# TELM0005_TempSenseHIGH_BCR.net
KiCad netlist of a schematic drawn in Altium Designer
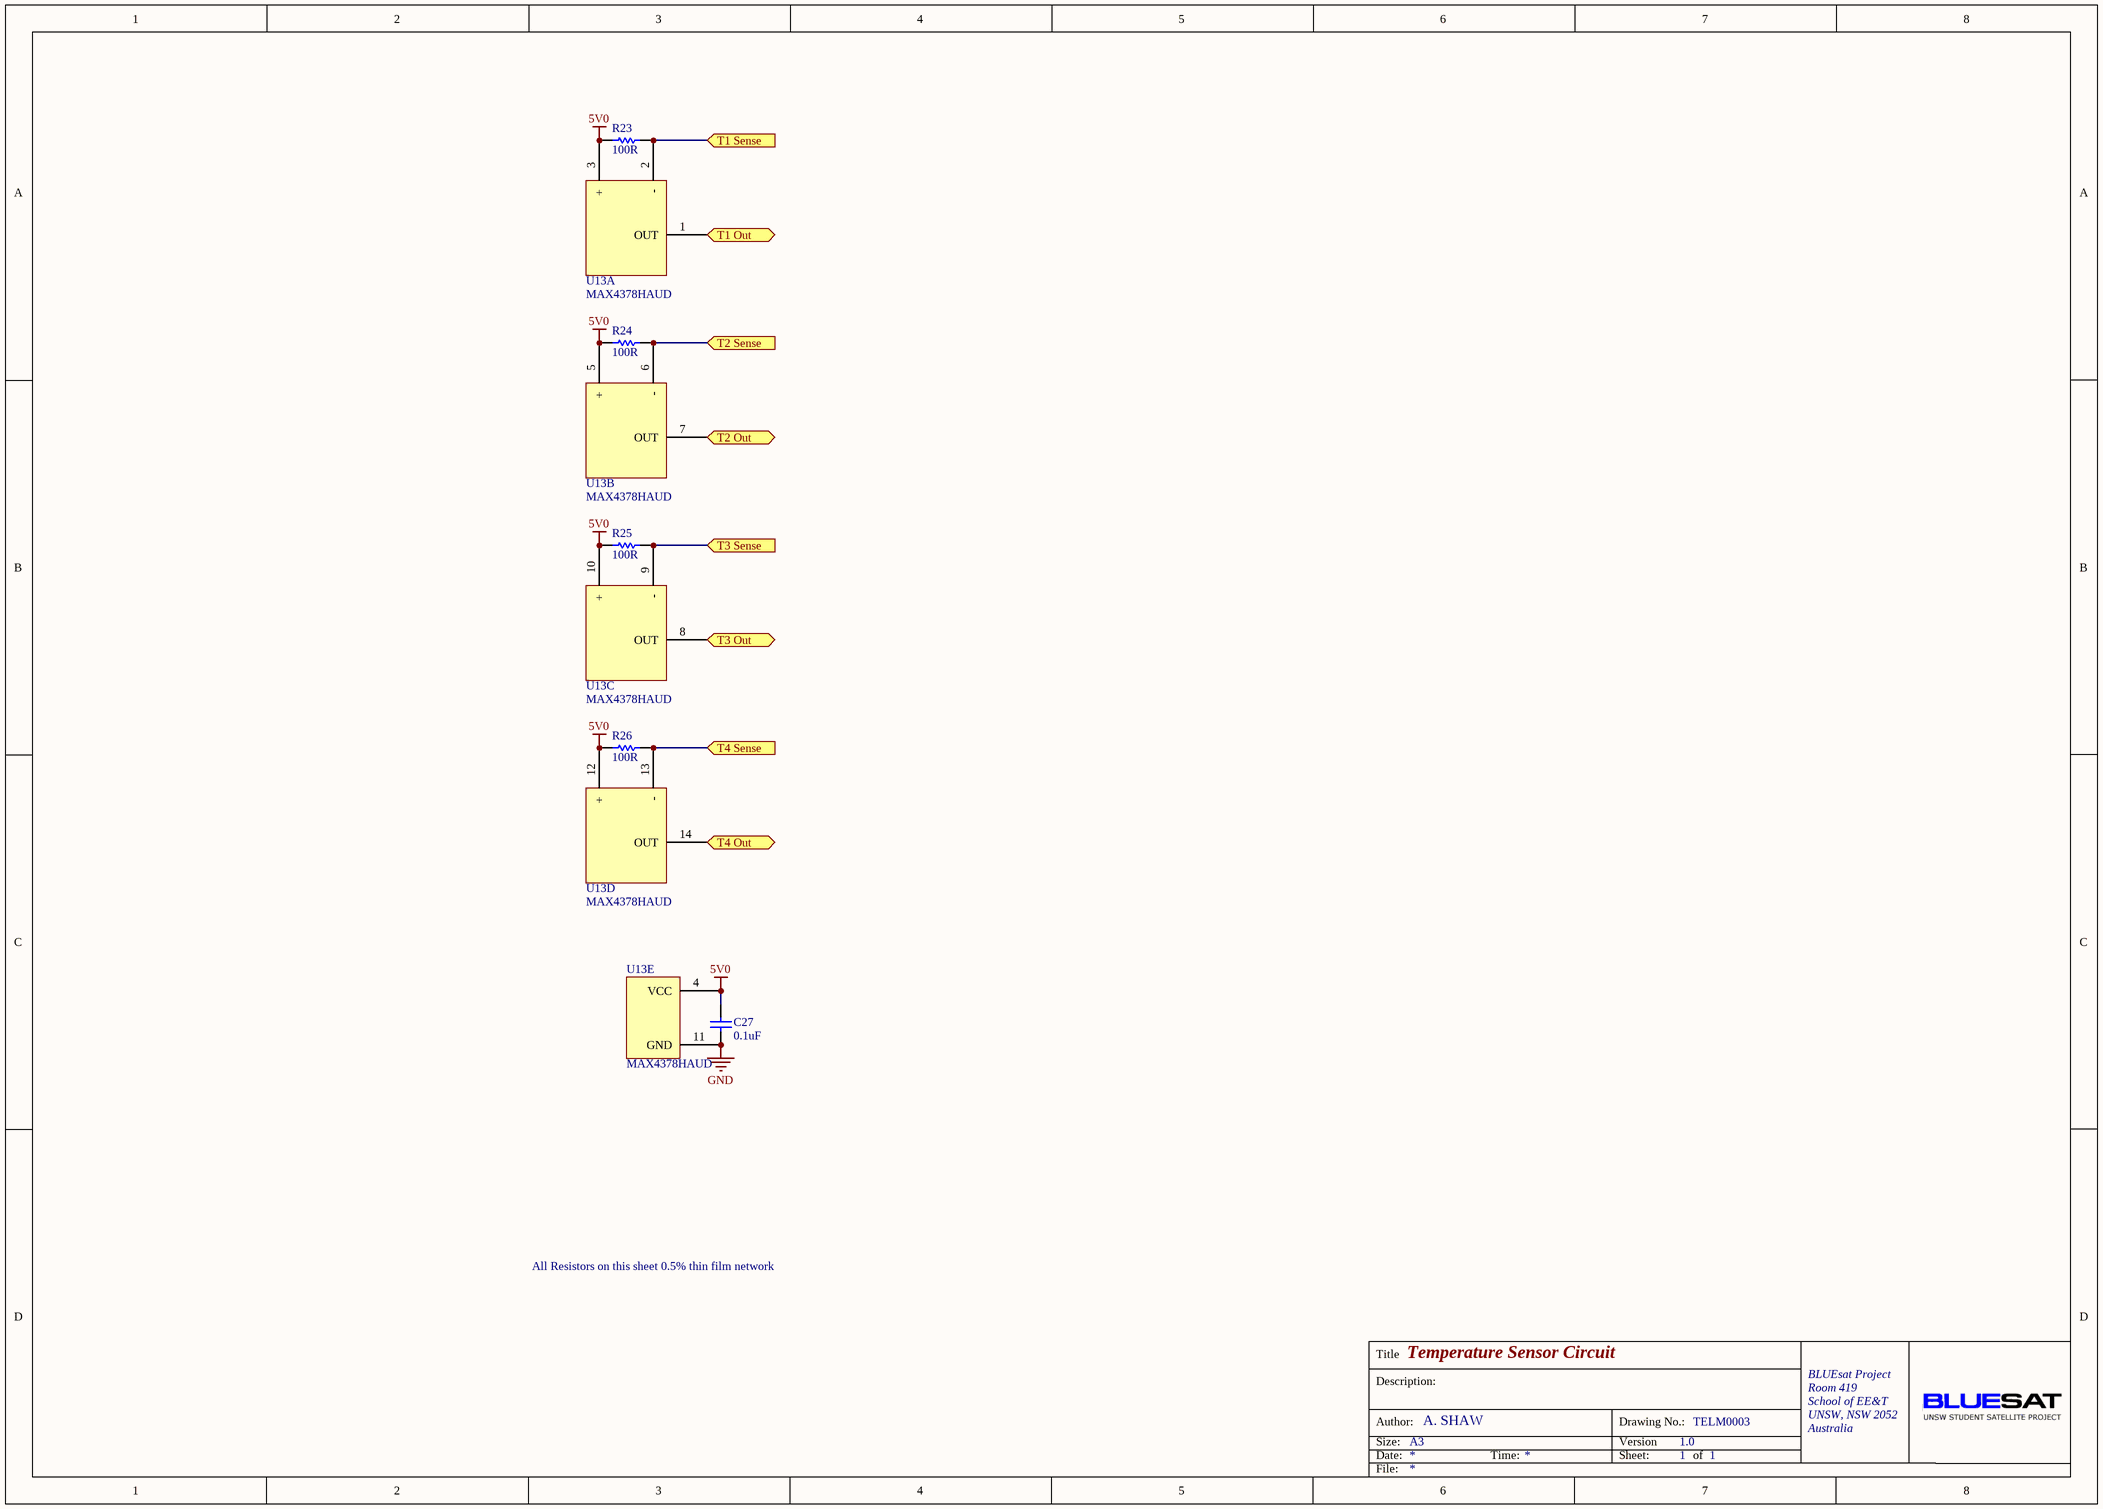
[diagram p0: TELM0005_TempSenseHIGH_BCR.SchDoc]

(export (version "E")
  (design (tool "Eeschema 10.0.6"))
  (components
    (comp (ref "C27")
      (value "0.1uF")
      (footprint "CAPC2012M")
      (description "Capacitor")
      (fields (field (name "Comment") "Cap") (field (name "PUBLISHER") "Altium Limited"))
      (libsource (lib "Miscellaneous Devices") (part "Cap"))
    )
    (comp (ref "R23")
      (value "100R")
      (footprint "RESC2012M")
      (description "Resistor")
      (fields (field (name "Comment") "Res1") (field (name "PUBLISHER") "Altium Limited"))
      (libsource (lib "Miscellaneous Devices") (part "Res1"))
    )
    (comp (ref "R24")
      (value "100R")
      (footprint "RESC2012M")
      (description "Resistor")
      (fields (field (name "Comment") "Res1") (field (name "PUBLISHER") "Altium Limited"))
      (libsource (lib "Miscellaneous Devices") (part "Res1"))
    )
    (comp (ref "R25")
      (value "100R")
      (footprint "RESC2012M")
      (description "Resistor")
      (fields (field (name "Comment") "Res1") (field (name "PUBLISHER") "Altium Limited"))
      (libsource (lib "Miscellaneous Devices") (part "Res1"))
    )
    (comp (ref "R26")
      (value "100R")
      (footprint "RESC2012M")
      (description "Resistor")
      (fields (field (name "Comment") "Res1") (field (name "PUBLISHER") "Altium Limited"))
      (libsource (lib "Miscellaneous Devices") (part "Res1"))
    )
    (comp (ref "U13")
      (value "MAX4378HAUD")
      (footprint "TSOP65P640-14AN")
      (libsource (lib "Base") (part "MAX4378HAUD"))
    )
  )
  (nets
    (net (code "1") (name "/T1 Out") (class "Default")
      (node (ref "U13") (pin "1") (pinfunction "OUT_1") (pintype "passive"))
    )
    (net (code "2") (name "/T1 Sense") (class "Default")
      (node (ref "R23") (pin "2") (pinfunction "2_2") (pintype "passive"))
      (node (ref "U13") (pin "2") (pinfunction "-_2") (pintype "passive"))
    )
    (net (code "3") (name "/T2 Out") (class "Default")
      (node (ref "U13") (pin "7") (pinfunction "OUT_7") (pintype "passive"))
    )
    (net (code "4") (name "/T2 Sense") (class "Default")
      (node (ref "R24") (pin "2") (pinfunction "2_2") (pintype "passive"))
      (node (ref "U13") (pin "6") (pinfunction "-_6") (pintype "passive"))
    )
    (net (code "5") (name "/T3 Out") (class "Default")
      (node (ref "U13") (pin "8") (pinfunction "OUT_8") (pintype "passive"))
    )
    (net (code "6") (name "/T3 Sense") (class "Default")
      (node (ref "R25") (pin "2") (pinfunction "2_2") (pintype "passive"))
      (node (ref "U13") (pin "9") (pinfunction "-_9") (pintype "passive"))
    )
    (net (code "7") (name "/T4 Out") (class "Default")
      (node (ref "U13") (pin "14") (pinfunction "OUT_14") (pintype "passive"))
    )
    (net (code "8") (name "/T4 Sense") (class "Default")
      (node (ref "R26") (pin "2") (pinfunction "2_2") (pintype "passive"))
      (node (ref "U13") (pin "13") (pinfunction "-_13") (pintype "passive"))
    )
    (net (code "9") (name "5V0") (class "Default")
      (node (ref "C27") (pin "2") (pinfunction "2_2") (pintype "passive"))
      (node (ref "R23") (pin "1") (pinfunction "1_1") (pintype "passive"))
      (node (ref "R24") (pin "1") (pinfunction "1_1") (pintype "passive"))
      (node (ref "R25") (pin "1") (pinfunction "1_1") (pintype "passive"))
      (node (ref "R26") (pin "1") (pinfunction "1_1") (pintype "passive"))
      (node (ref "U13") (pin "10") (pinfunction "+_10") (pintype "passive"))
      (node (ref "U13") (pin "12") (pinfunction "+_12") (pintype "passive"))
      (node (ref "U13") (pin "3") (pinfunction "+_3") (pintype "passive"))
      (node (ref "U13") (pin "4") (pinfunction "VCC_4") (pintype "passive"))
      (node (ref "U13") (pin "5") (pinfunction "+_5") (pintype "passive"))
    )
    (net (code "10") (name "GND") (class "Default")
      (node (ref "C27") (pin "1") (pinfunction "1_1") (pintype "passive"))
      (node (ref "U13") (pin "11") (pinfunction "GND_11") (pintype "passive"))
    )
  )
)
